# ComBadge.net
KiCad netlist of a schematic drawn in EasyEDA Pro
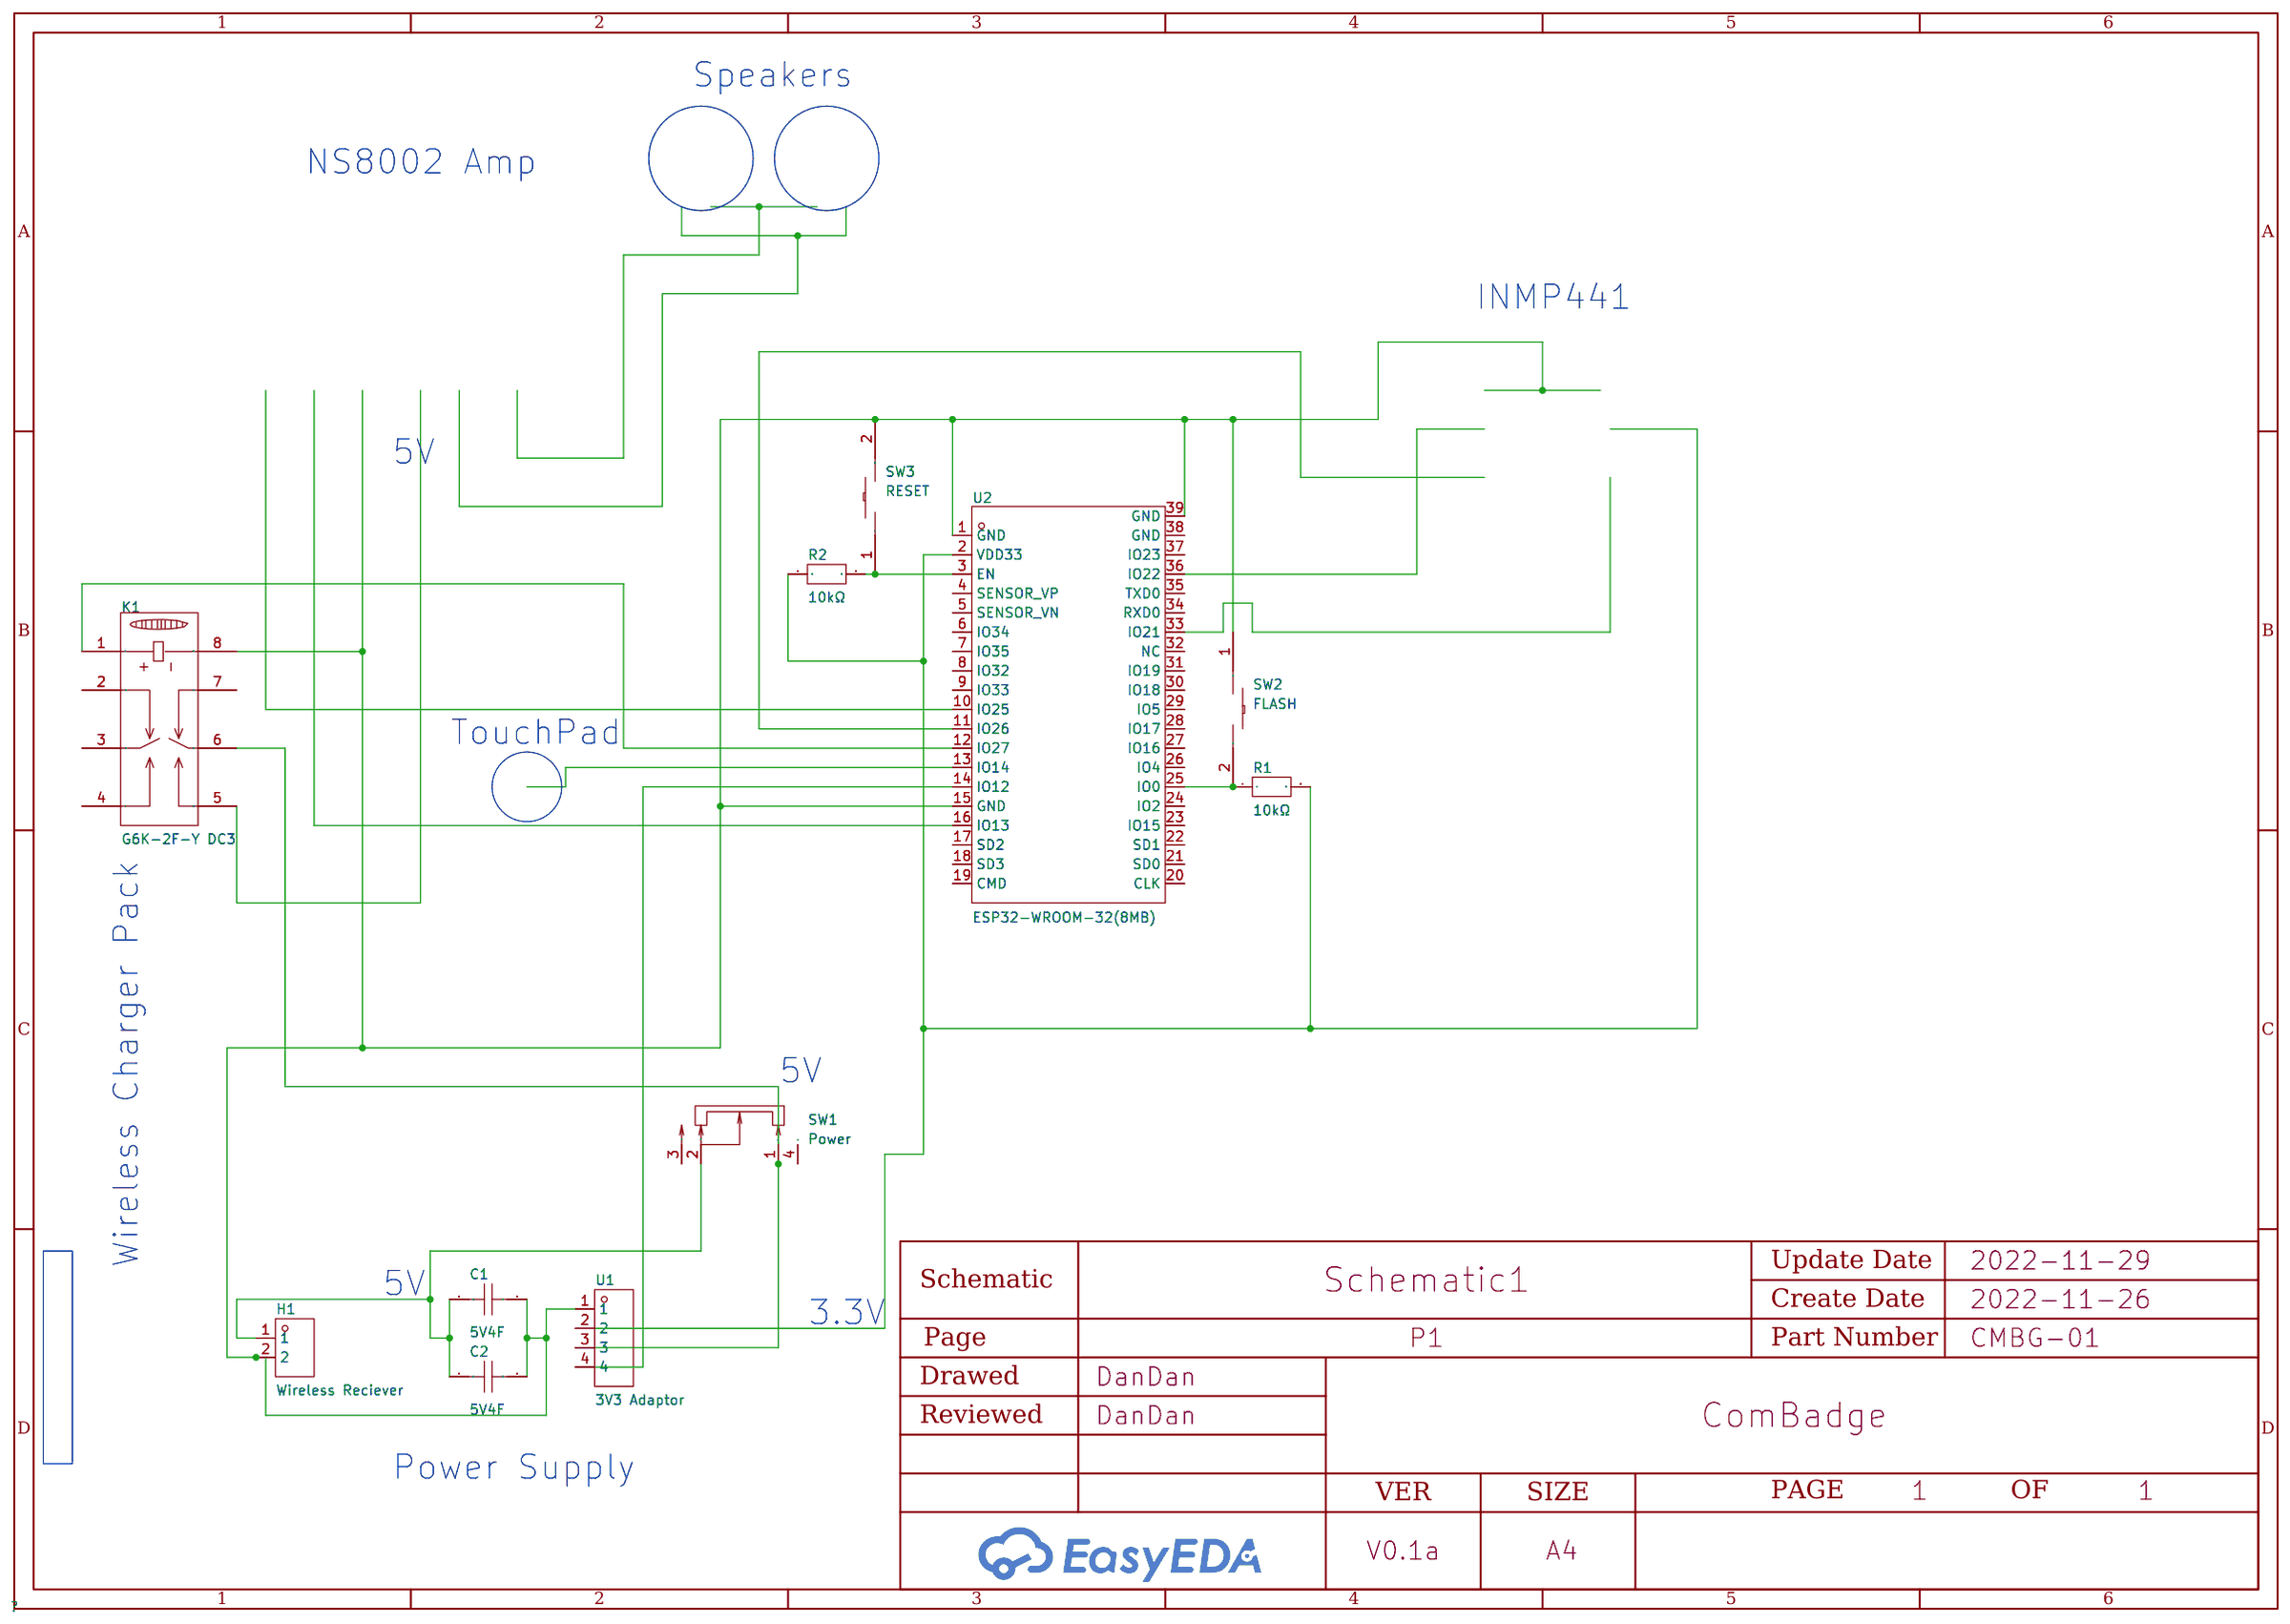
[diagram p0: schematic sheet]

(export (version "E")
  (design (tool "Eeschema 10.0.6"))
  (components
    (comp (ref "C1") (value "4F") (footprint "easyedapro:C0805") (libsource (lib "easyedapro") (part "CAP")))
    (comp (ref "C2")
      (value "100nF")
      (footprint "easyedapro:C0805")
      (libsource (lib "easyedapro") (part "CAP"))
    )
    (comp (ref "H1")
      (value "Wireless Reciever")
      (footprint "easyedapro:HDR-TH_2P-P2.00-V-M")
      (fields (field (name "Manufacturer Part") "MTP220-1102S1") (field (name "Manufacturer") "MINTRON(明硕)"))
      (libsource (lib "easyedapro") (part "MTP220-1102S1"))
    )
    (comp (ref "K1")
      (value "G6K-2F-Y DC3")
      (footprint "easyedapro:RELAY-SMD_G6K-2F-Y")
      (description "Contact Form:DPDT Coil Type:Nolocking")
      (fields (field (name "Manufacturer") "OMRON(欧姆龙)"))
      (libsource (lib "easyedapro") (part "G6K-2F-Y3VDC"))
    )
    (comp (ref "R1")
      (value "10kΩ")
      (footprint "easyedapro:R0402")
      (description "Resistance: Tolerance:±5% Tolerance:±5%")
      (fields (field (name "Manufacturer Part") "SCR0402J10K") (field (name "Manufacturer") "VO(翔胜)"))
      (libsource (lib "easyedapro") (part "SCR0402J10K"))
    )
    (comp (ref "R2")
      (value "10kΩ")
      (footprint "easyedapro:R0402")
      (description "Resistance: Tolerance:±5% Tolerance:±5%")
      (fields (field (name "Manufacturer Part") "SCR0402J10K") (field (name "Manufacturer") "VO(翔胜)"))
      (libsource (lib "easyedapro") (part "SCR0402J10K"))
    )
    (comp (ref "SW1")
      (value "Power")
      (footprint "easyedapro:SW-SMD_PCM12SMTR")
      (fields (field (name "Manufacturer Part") "PCM12SMTR") (field (name "Manufacturer") "C&K"))
      (libsource (lib "easyedapro") (part "PCM12SMTR"))
    )
    (comp (ref "SW2")
      (value "FLASH")
      (footprint "easyedapro:KEY-SMD_L4.0-W2.9-LS4.8")
      (fields (field (name "Manufacturer Part") "MPTFP2-V-T/R") (field (name "Manufacturer") "台湾圜达"))
      (libsource (lib "easyedapro") (part "MPTFP2-V-T/R"))
    )
    (comp (ref "SW3")
      (value "RESET")
      (footprint "easyedapro:KEY-SMD_L4.0-W2.9-LS4.8")
      (fields (field (name "Manufacturer Part") "MPTFP2-V-T/R") (field (name "Manufacturer") "台湾圜达"))
      (libsource (lib "easyedapro") (part "MPTFP2-V-T/R"))
    )
    (comp (ref "U1")
      (value "3V3 Adaptor")
      (footprint "easyedapro:CONN-TH_M2553R-04P")
      (fields (field (name "Manufacturer Part") "杜邦2.54-4A弯针") (field (name "Manufacturer") "BOOMELE(博穆精密)"))
      (libsource (lib "easyedapro") (part "2.54间距4P杜邦带锁弯针"))
    )
    (comp (ref "U2")
      (value "ESP32-WROOM-32(8MB)")
      (footprint "easyedapro:WIFIM-SMD_39P-L25.5-W18.0-P1.27")
      (fields (field (name "Manufacturer") "ESPRESSIF(乐鑫)"))
      (libsource (lib "easyedapro") (part "ESP32-WROOM-32(8MB)"))
    )
  )
  (nets
    (net (code "1") (name "Net-(C1-Pad1)") (class "Default")
      (node (ref "C1") (pin "1") (pinfunction "1_1") (pintype "input"))
      (node (ref "C2") (pin "1") (pinfunction "1_1") (pintype "input"))
      (node (ref "H1") (pin "2") (pinfunction "2_2") (pintype "input"))
      (node (ref "K1") (pin "8") (pinfunction "8_8") (pintype "input"))
      (node (ref "SW2") (pin "1") (pinfunction "1_1") (pintype "input"))
      (node (ref "SW3") (pin "2") (pinfunction "2_2") (pintype "input"))
      (node (ref "U1") (pin "1") (pinfunction "1_1") (pintype "input"))
      (node (ref "U2") (pin "1") (pinfunction "GND_1") (pintype "input"))
      (node (ref "U2") (pin "15") (pinfunction "GND_15") (pintype "input"))
      (node (ref "U2") (pin "39") (pinfunction "GND_39") (pintype "input"))
    )
    (net (code "2") (name "Net-(C1-Pad2)") (class "Default")
      (node (ref "C1") (pin "2") (pinfunction "2_2") (pintype "input"))
      (node (ref "C2") (pin "2") (pinfunction "2_2") (pintype "input"))
      (node (ref "H1") (pin "1") (pinfunction "1_1") (pintype "input"))
      (node (ref "SW1") (pin "2") (pinfunction "2_2") (pintype "input"))
    )
    (net (code "3") (name "Net-(K1-Pad6)") (class "Default")
      (node (ref "K1") (pin "6") (pinfunction "6_6") (pintype "input"))
      (node (ref "SW1") (pin "1") (pinfunction "1_1") (pintype "input"))
      (node (ref "U1") (pin "3") (pinfunction "3_3") (pintype "input"))
    )
    (net (code "4") (name "Net-(U2-EN)") (class "Default")
      (node (ref "R2") (pin "2") (pinfunction "2_2") (pintype "input"))
      (node (ref "SW3") (pin "1") (pinfunction "1_1") (pintype "input"))
      (node (ref "U2") (pin "3") (pinfunction "EN_3") (pintype "input"))
    )
    (net (code "5") (name "Net-(U2-IO0)") (class "Default")
      (node (ref "R1") (pin "1") (pinfunction "1_1") (pintype "input"))
      (node (ref "SW2") (pin "2") (pinfunction "2_2") (pintype "input"))
      (node (ref "U2") (pin "25") (pinfunction "IO0_25") (pintype "input"))
    )
    (net (code "6") (name "Net-(U2-IO12)") (class "Default")
      (node (ref "U1") (pin "4") (pinfunction "4_4") (pintype "input"))
      (node (ref "U2") (pin "14") (pinfunction "IO12_14") (pintype "input"))
    )
    (net (code "7") (name "Net-(U2-IO27)") (class "Default")
      (node (ref "K1") (pin "1") (pinfunction "1_1") (pintype "input"))
      (node (ref "U2") (pin "12") (pinfunction "IO27_12") (pintype "input"))
    )
    (net (code "8") (name "Net-(U2-VDD33)") (class "Default")
      (node (ref "R1") (pin "2") (pinfunction "2_2") (pintype "input"))
      (node (ref "R2") (pin "1") (pinfunction "1_1") (pintype "input"))
      (node (ref "U1") (pin "2") (pinfunction "2_2") (pintype "input"))
      (node (ref "U2") (pin "2") (pinfunction "VDD33_2") (pintype "input"))
    )
    (net (code "9") (name "unconnected-(K1-Pad2)") (class "Default")
      (node (ref "K1") (pin "2") (pinfunction "2_2") (pintype "input"))
    )
    (net (code "10") (name "unconnected-(K1-Pad3)") (class "Default")
      (node (ref "K1") (pin "3") (pinfunction "3_3") (pintype "input"))
    )
    (net (code "11") (name "unconnected-(K1-Pad4)") (class "Default")
      (node (ref "K1") (pin "4") (pinfunction "4_4") (pintype "input"))
    )
    (net (code "12") (name "unconnected-(K1-Pad5)") (class "Default")
      (node (ref "K1") (pin "5") (pinfunction "5_5") (pintype "input"))
    )
    (net (code "13") (name "unconnected-(K1-Pad7)") (class "Default")
      (node (ref "K1") (pin "7") (pinfunction "7_7") (pintype "input"))
    )
    (net (code "14") (name "unconnected-(SW1-Pad3)") (class "Default")
      (node (ref "SW1") (pin "3") (pinfunction "3_3") (pintype "input"))
    )
    (net (code "15") (name "unconnected-(SW1-Pad4)") (class "Default")
      (node (ref "SW1") (pin "4") (pinfunction "4_4") (pintype "input"))
    )
    (net (code "16") (name "unconnected-(U2-CLK-Pad20)") (class "Default")
      (node (ref "U2") (pin "20") (pinfunction "CLK_20") (pintype "input"))
    )
    (net (code "17") (name "unconnected-(U2-CMD-Pad19)") (class "Default")
      (node (ref "U2") (pin "19") (pinfunction "CMD_19") (pintype "input"))
    )
    (net (code "18") (name "unconnected-(U2-GND-Pad38)") (class "Default")
      (node (ref "U2") (pin "38") (pinfunction "GND_38") (pintype "input"))
    )
    (net (code "19") (name "unconnected-(U2-IO2-Pad24)") (class "Default")
      (node (ref "U2") (pin "24") (pinfunction "IO2_24") (pintype "input"))
    )
    (net (code "20") (name "unconnected-(U2-IO4-Pad26)") (class "Default")
      (node (ref "U2") (pin "26") (pinfunction "IO4_26") (pintype "input"))
    )
    (net (code "21") (name "unconnected-(U2-IO5-Pad29)") (class "Default")
      (node (ref "U2") (pin "29") (pinfunction "IO5_29") (pintype "input"))
    )
    (net (code "22") (name "unconnected-(U2-IO13-Pad16)") (class "Default")
      (node (ref "U2") (pin "16") (pinfunction "IO13_16") (pintype "input"))
    )
    (net (code "23") (name "unconnected-(U2-IO14-Pad13)") (class "Default")
      (node (ref "U2") (pin "13") (pinfunction "IO14_13") (pintype "input"))
    )
    (net (code "24") (name "unconnected-(U2-IO15-Pad23)") (class "Default")
      (node (ref "U2") (pin "23") (pinfunction "IO15_23") (pintype "input"))
    )
    (net (code "25") (name "unconnected-(U2-IO16-Pad27)") (class "Default")
      (node (ref "U2") (pin "27") (pinfunction "IO16_27") (pintype "input"))
    )
    (net (code "26") (name "unconnected-(U2-IO17-Pad28)") (class "Default")
      (node (ref "U2") (pin "28") (pinfunction "IO17_28") (pintype "input"))
    )
    (net (code "27") (name "unconnected-(U2-IO18-Pad30)") (class "Default")
      (node (ref "U2") (pin "30") (pinfunction "IO18_30") (pintype "input"))
    )
    (net (code "28") (name "unconnected-(U2-IO19-Pad31)") (class "Default")
      (node (ref "U2") (pin "31") (pinfunction "IO19_31") (pintype "input"))
    )
    (net (code "29") (name "unconnected-(U2-IO21-Pad33)") (class "Default")
      (node (ref "U2") (pin "33") (pinfunction "IO21_33") (pintype "input"))
    )
    (net (code "30") (name "unconnected-(U2-IO22-Pad36)") (class "Default")
      (node (ref "U2") (pin "36") (pinfunction "IO22_36") (pintype "input"))
    )
    (net (code "31") (name "unconnected-(U2-IO23-Pad37)") (class "Default")
      (node (ref "U2") (pin "37") (pinfunction "IO23_37") (pintype "input"))
    )
    (net (code "32") (name "unconnected-(U2-IO25-Pad10)") (class "Default")
      (node (ref "U2") (pin "10") (pinfunction "IO25_10") (pintype "input"))
    )
    (net (code "33") (name "unconnected-(U2-IO26-Pad11)") (class "Default")
      (node (ref "U2") (pin "11") (pinfunction "IO26_11") (pintype "input"))
    )
    (net (code "34") (name "unconnected-(U2-IO32-Pad8)") (class "Default")
      (node (ref "U2") (pin "8") (pinfunction "IO32_8") (pintype "input"))
    )
    (net (code "35") (name "unconnected-(U2-IO33-Pad9)") (class "Default")
      (node (ref "U2") (pin "9") (pinfunction "IO33_9") (pintype "input"))
    )
    (net (code "36") (name "unconnected-(U2-IO34-Pad6)") (class "Default")
      (node (ref "U2") (pin "6") (pinfunction "IO34_6") (pintype "input"))
    )
    (net (code "37") (name "unconnected-(U2-IO35-Pad7)") (class "Default")
      (node (ref "U2") (pin "7") (pinfunction "IO35_7") (pintype "input"))
    )
    (net (code "38") (name "unconnected-(U2-NC-Pad32)") (class "Default")
      (node (ref "U2") (pin "32") (pinfunction "NC_32") (pintype "input"))
    )
    (net (code "39") (name "unconnected-(U2-RXD0-Pad34)") (class "Default")
      (node (ref "U2") (pin "34") (pinfunction "RXD0_34") (pintype "input"))
    )
    (net (code "40") (name "unconnected-(U2-SD0-Pad21)") (class "Default")
      (node (ref "U2") (pin "21") (pinfunction "SD0_21") (pintype "input"))
    )
    (net (code "41") (name "unconnected-(U2-SD1-Pad22)") (class "Default")
      (node (ref "U2") (pin "22") (pinfunction "SD1_22") (pintype "input"))
    )
    (net (code "42") (name "unconnected-(U2-SD2-Pad17)") (class "Default")
      (node (ref "U2") (pin "17") (pinfunction "SD2_17") (pintype "input"))
    )
    (net (code "43") (name "unconnected-(U2-SD3-Pad18)") (class "Default")
      (node (ref "U2") (pin "18") (pinfunction "SD3_18") (pintype "input"))
    )
    (net (code "44") (name "unconnected-(U2-SENSOR_VN-Pad5)") (class "Default")
      (node (ref "U2") (pin "5") (pinfunction "SENSOR_VN_5") (pintype "input"))
    )
    (net (code "45") (name "unconnected-(U2-SENSOR_VP-Pad4)") (class "Default")
      (node (ref "U2") (pin "4") (pinfunction "SENSOR_VP_4") (pintype "input"))
    )
    (net (code "46") (name "unconnected-(U2-TXD0-Pad35)") (class "Default")
      (node (ref "U2") (pin "35") (pinfunction "TXD0_35") (pintype "input"))
    )
  )
)
